# PnP-Expansion-V1.net
KiCad netlist of a schematic drawn in EAGLE
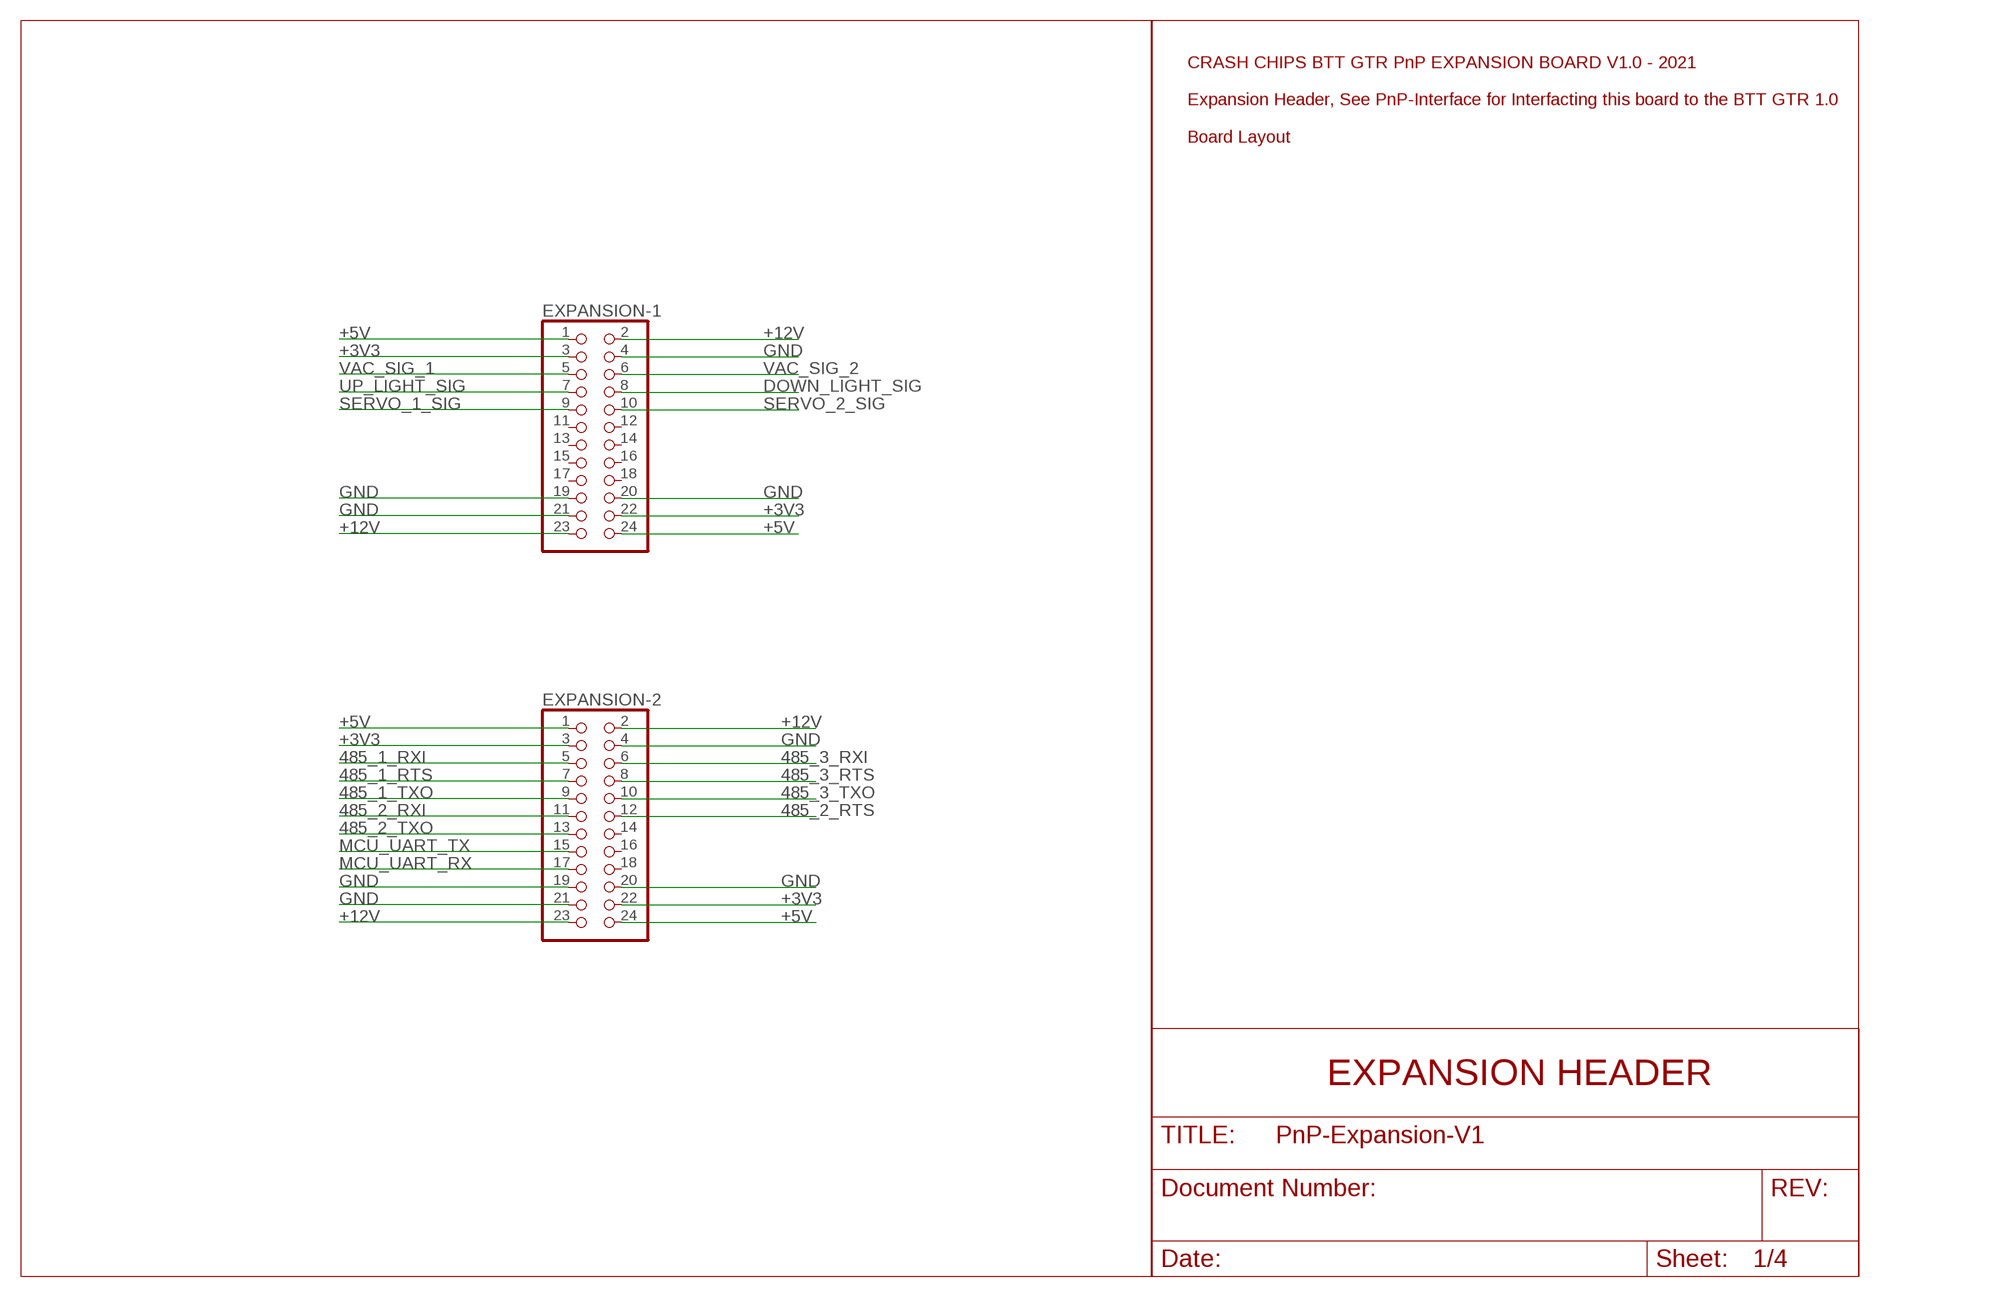
[diagram p0: schematic, sheet 1]
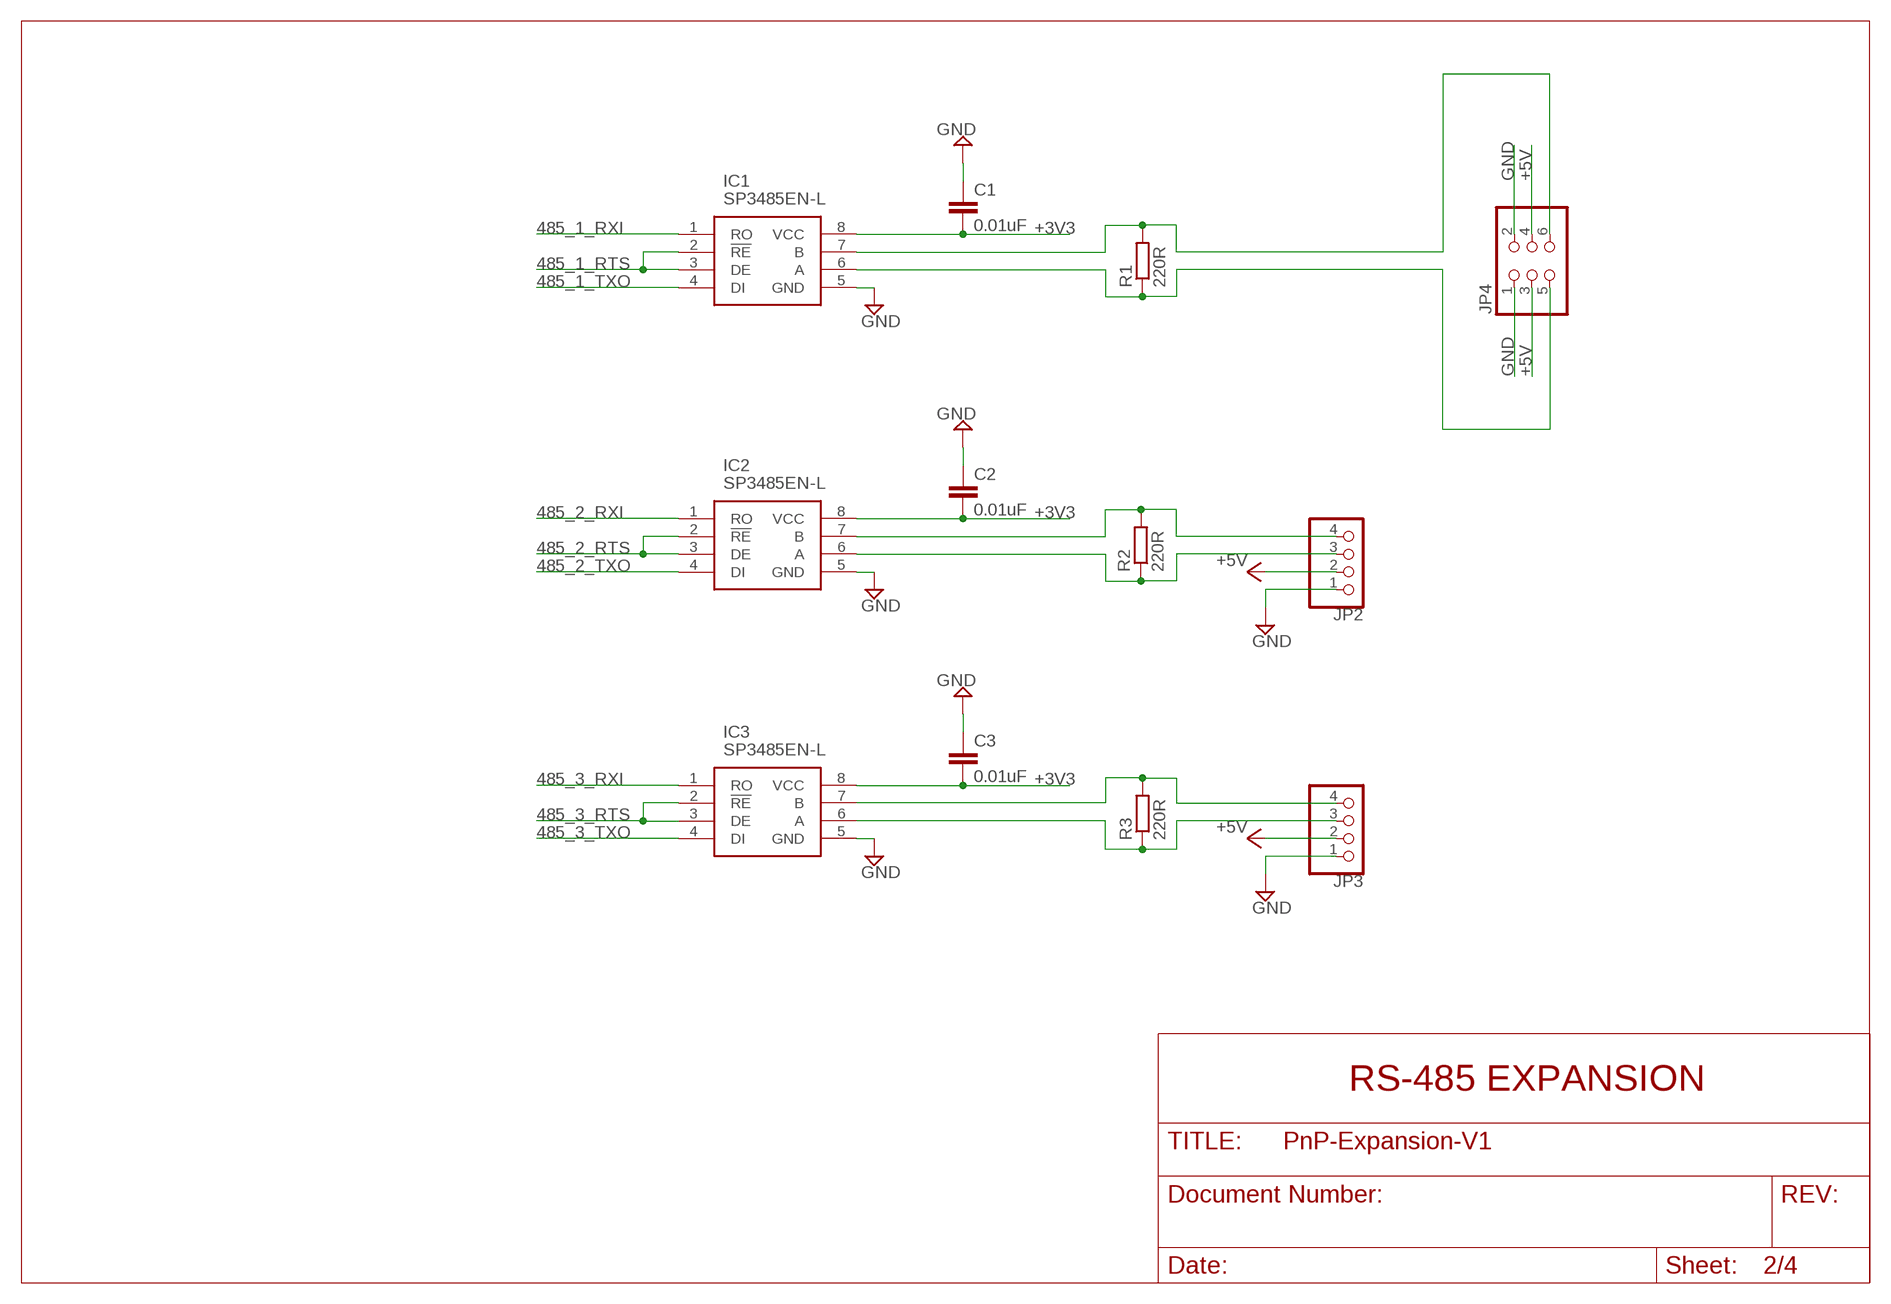
[diagram p1: schematic, sheet 2]
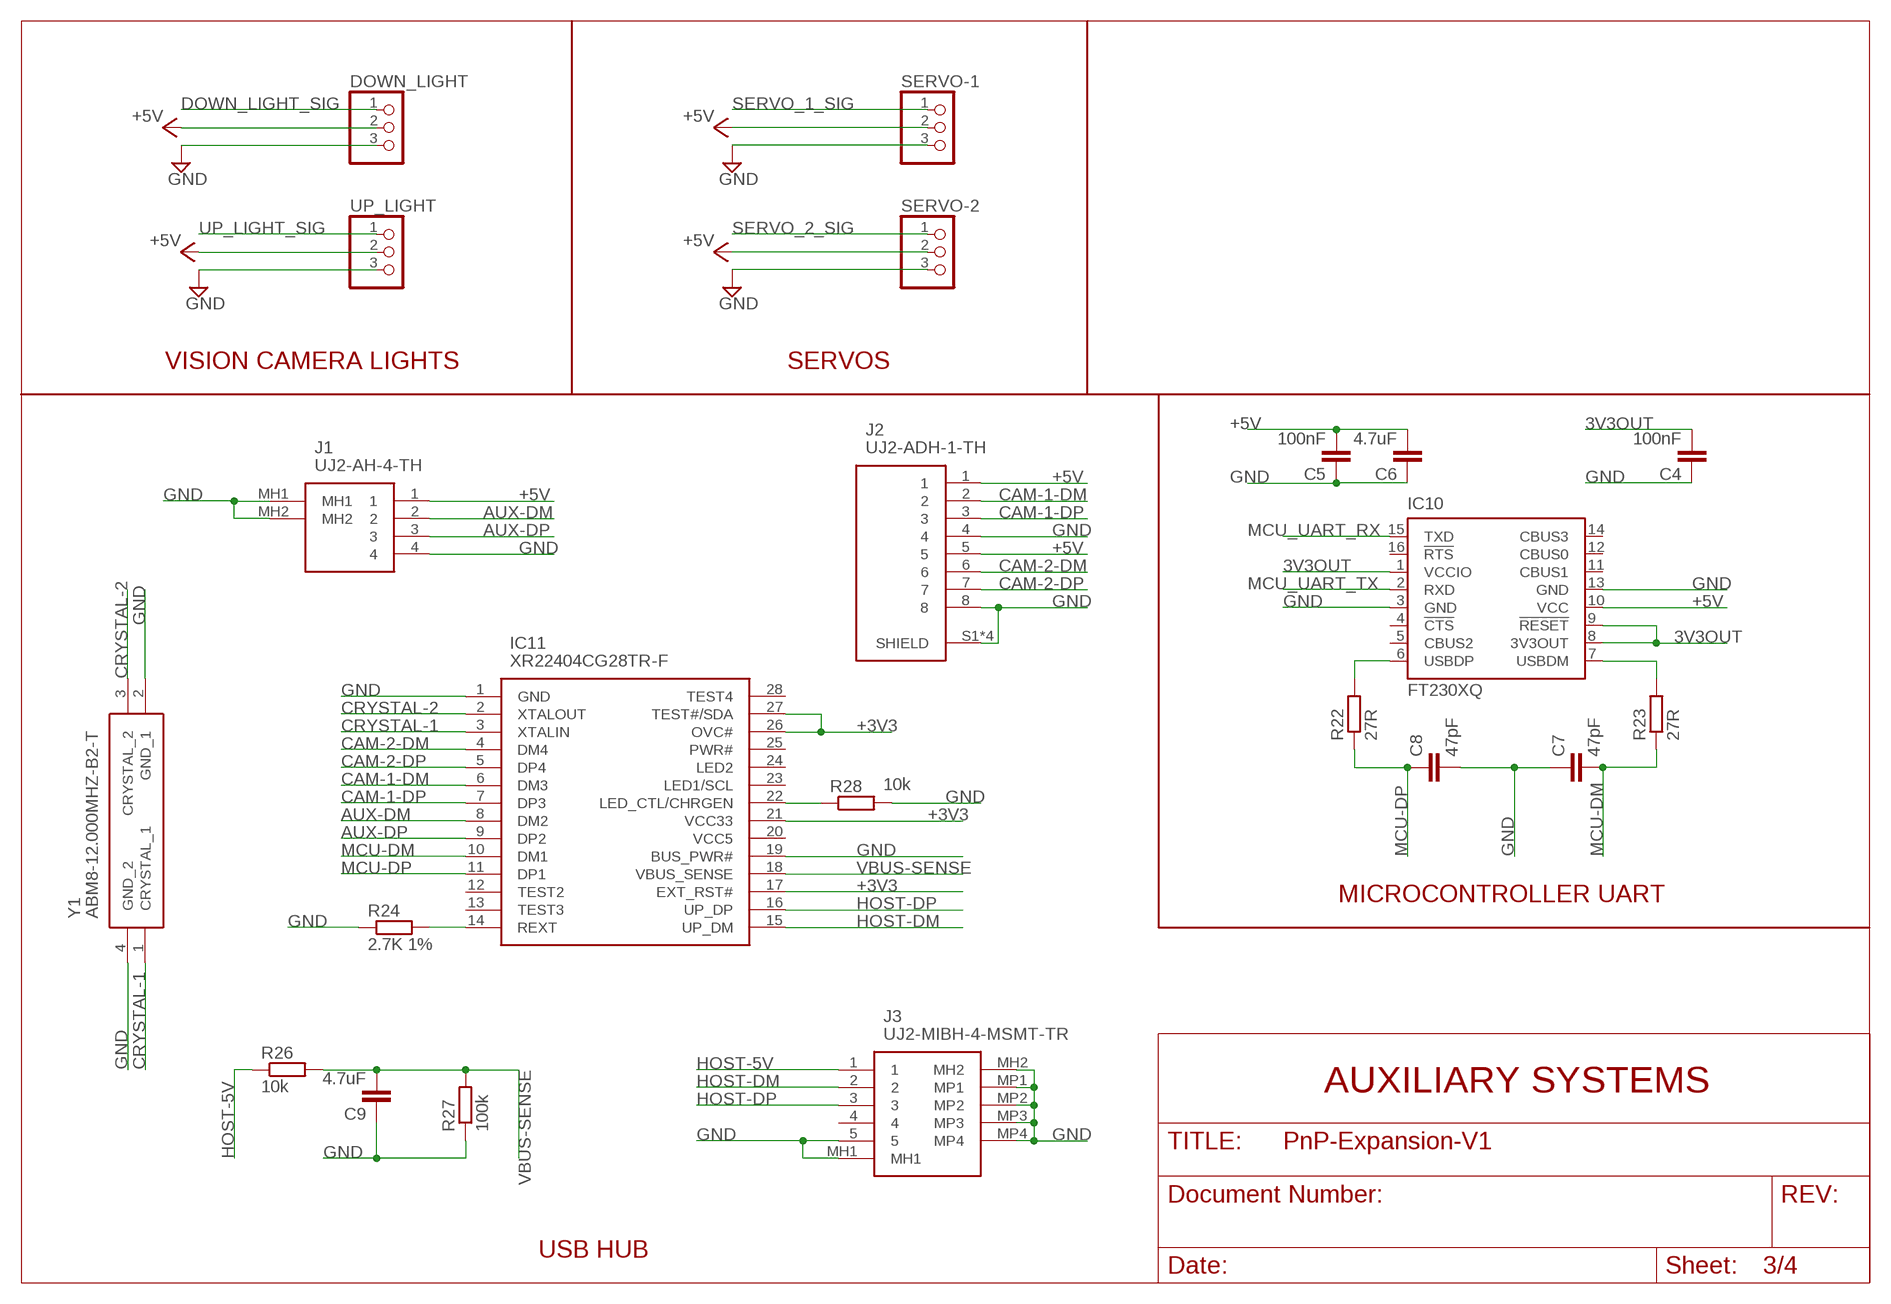
[diagram p2: schematic, sheet 3]
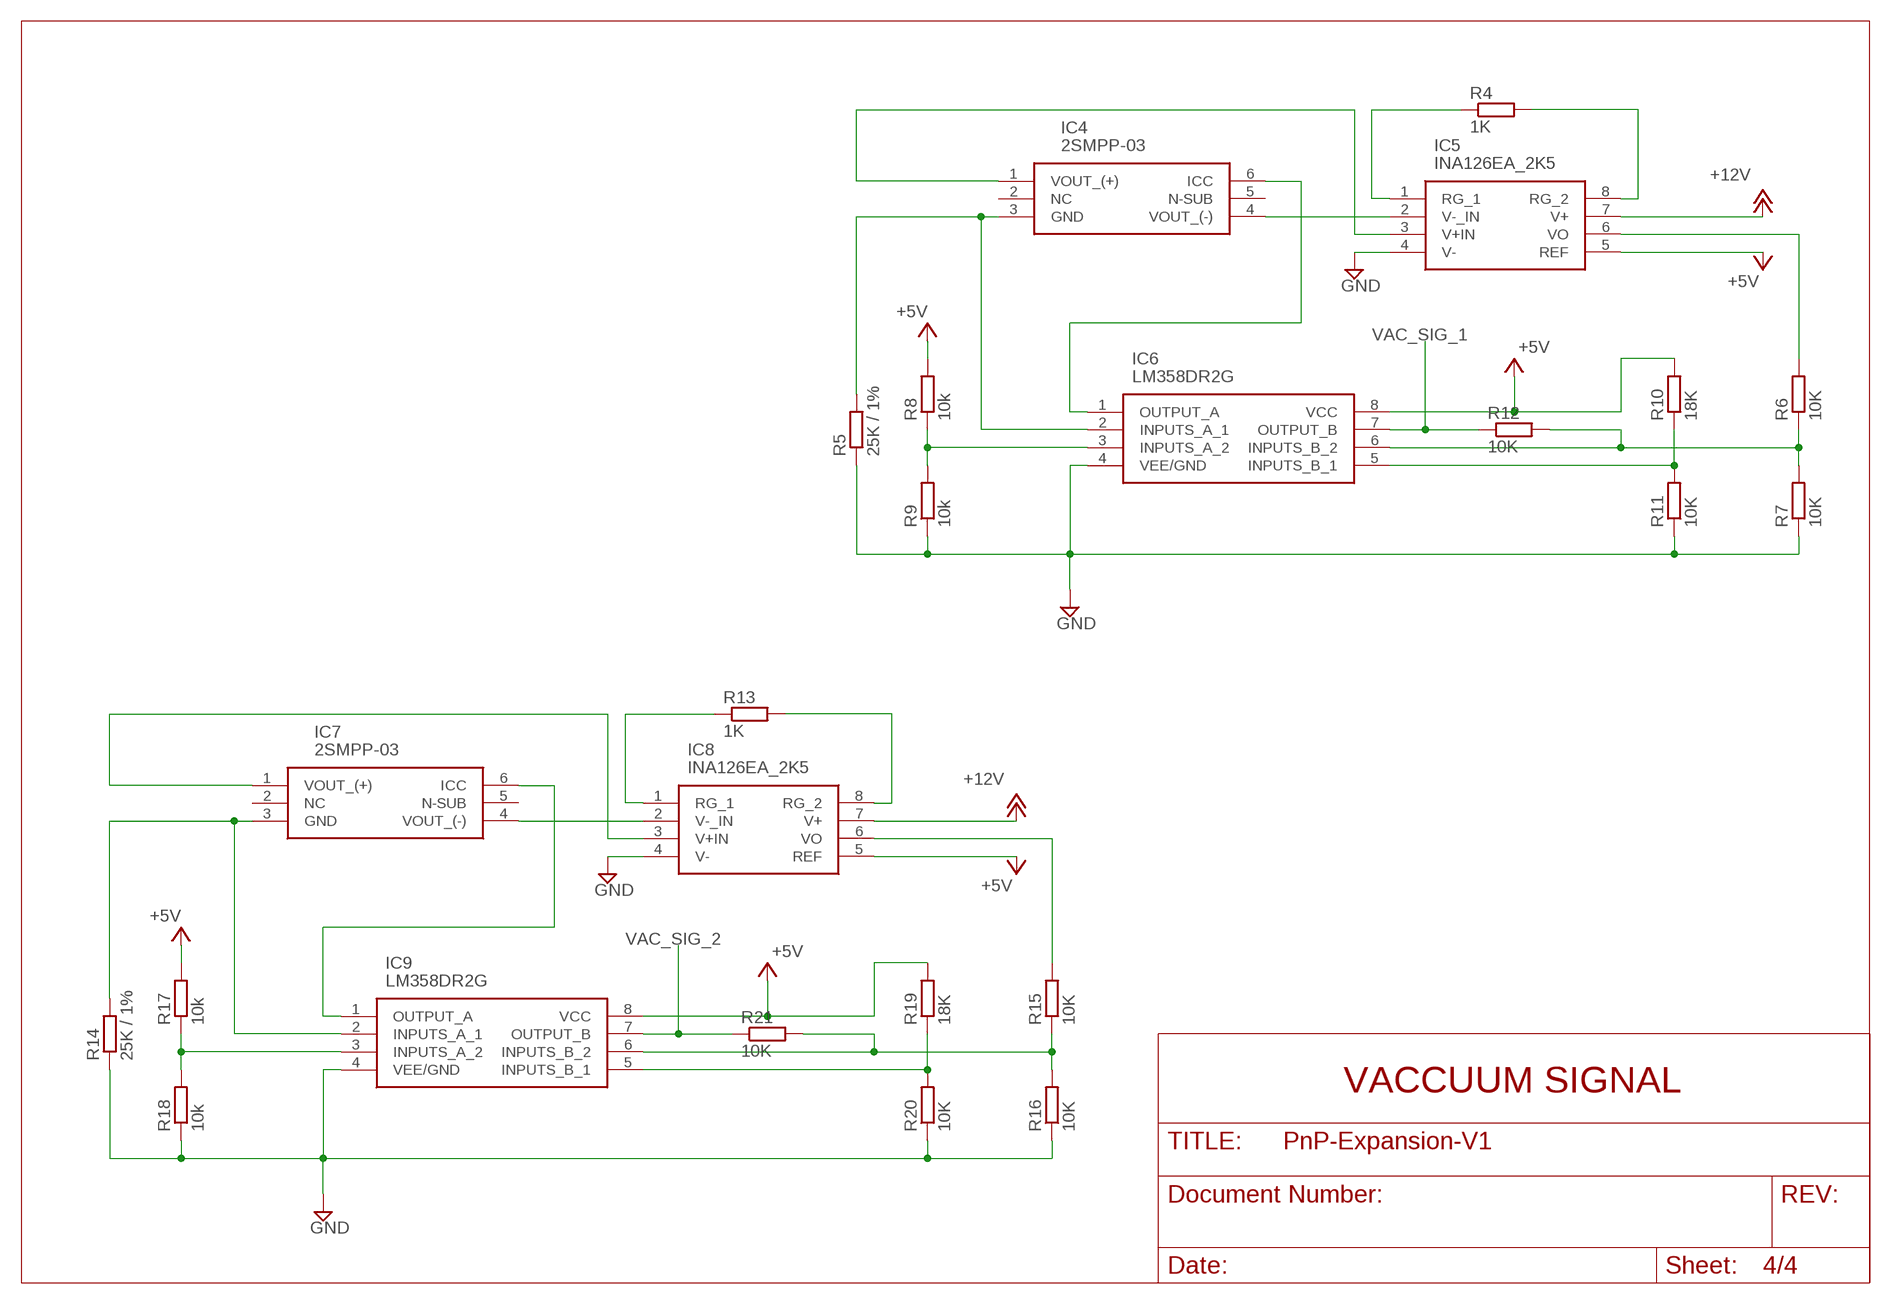
[diagram p3: schematic, sheet 4]

(export (version "E")
  (design (tool "Eeschema 10.0.6"))
  (components
    (comp (ref "IC4")
      (value "2SMPP-03")
      (footprint "eagle-import:2SMPP03")
      (fields (field (name "MOUSER_PART_NUMBER") "653-2SMPP-03"))
      (libsource (lib "eagle-import") (part "2SMPP-03"))
    )
    (comp (ref "IC5")
      (value "INA126EA_2K5")
      (footprint "eagle-import:SOP65P490X110-8N")
      (fields
        (field (name "ARROW_PART_NUMBER") "INA126EA/2K5")
        (field (name "MOUSER_PART_NUMBER") "595-INA126EA/2K5")
      )
      (libsource (lib "eagle-import") (part "INA126EA_2K5"))
    )
    (comp (ref "IC6")
      (value "LM358DR2G")
      (footprint "eagle-import:SOIC127P600X175-8N")
      (fields (field (name "MOUSER_PART_NUMBER") "863-LM358DR2G"))
      (libsource (lib "eagle-import") (part "LM358DR2G"))
    )
    (comp (ref "IC7")
      (value "2SMPP-03")
      (footprint "eagle-import:2SMPP03")
      (fields (field (name "MOUSER_PART_NUMBER") "653-2SMPP-03"))
      (libsource (lib "eagle-import") (part "2SMPP-03"))
    )
    (comp (ref "IC8")
      (value "INA126EA_2K5")
      (footprint "eagle-import:SOP65P490X110-8N")
      (fields
        (field (name "ARROW_PART_NUMBER") "INA126EA/2K5")
        (field (name "MOUSER_PART_NUMBER") "595-INA126EA/2K5")
      )
      (libsource (lib "eagle-import") (part "INA126EA_2K5"))
    )
    (comp (ref "IC9")
      (value "LM358DR2G")
      (footprint "eagle-import:SOIC127P600X175-8N")
      (fields (field (name "MOUSER_PART_NUMBER") "863-LM358DR2G"))
      (libsource (lib "eagle-import") (part "LM358DR2G"))
    )
    (comp (ref "R4")
      (value "1K")
      (footprint "eagle-import:M0805")
      (libsource (lib "eagle-import") (part "R-EU_M0805"))
    )
    (comp (ref "R5")
      (value "25K / 1%")
      (footprint "eagle-import:M0805")
      (libsource (lib "eagle-import") (part "R-EU_M0805"))
    )
    (comp (ref "R6")
      (value "10K")
      (footprint "eagle-import:M0805")
      (libsource (lib "eagle-import") (part "R-EU_M0805"))
    )
    (comp (ref "R7")
      (value "10K")
      (footprint "eagle-import:M0805")
      (libsource (lib "eagle-import") (part "R-EU_M0805"))
    )
    (comp (ref "R8")
      (value "10k")
      (footprint "eagle-import:M0805")
      (libsource (lib "eagle-import") (part "R-EU_M0805"))
    )
    (comp (ref "R9")
      (value "10k")
      (footprint "eagle-import:M0805")
      (libsource (lib "eagle-import") (part "R-EU_M0805"))
    )
    (comp (ref "R10")
      (value "18K")
      (footprint "eagle-import:M0805")
      (libsource (lib "eagle-import") (part "R-EU_M0805"))
    )
    (comp (ref "R11")
      (value "10K")
      (footprint "eagle-import:M0805")
      (libsource (lib "eagle-import") (part "R-EU_M0805"))
    )
    (comp (ref "R12")
      (value "10K")
      (footprint "eagle-import:M0805")
      (libsource (lib "eagle-import") (part "R-EU_M0805"))
    )
    (comp (ref "R13")
      (value "1K")
      (footprint "eagle-import:M0805")
      (libsource (lib "eagle-import") (part "R-EU_M0805"))
    )
    (comp (ref "R14")
      (value "25K / 1%")
      (footprint "eagle-import:M0805")
      (libsource (lib "eagle-import") (part "R-EU_M0805"))
    )
    (comp (ref "R15")
      (value "10K")
      (footprint "eagle-import:M0805")
      (libsource (lib "eagle-import") (part "R-EU_M0805"))
    )
    (comp (ref "R16")
      (value "10K")
      (footprint "eagle-import:M0805")
      (libsource (lib "eagle-import") (part "R-EU_M0805"))
    )
    (comp (ref "R17")
      (value "10k")
      (footprint "eagle-import:M0805")
      (libsource (lib "eagle-import") (part "R-EU_M0805"))
    )
    (comp (ref "R18")
      (value "10k")
      (footprint "eagle-import:M0805")
      (libsource (lib "eagle-import") (part "R-EU_M0805"))
    )
    (comp (ref "R19")
      (value "18K")
      (footprint "eagle-import:M0805")
      (libsource (lib "eagle-import") (part "R-EU_M0805"))
    )
    (comp (ref "R20")
      (value "10K")
      (footprint "eagle-import:M0805")
      (libsource (lib "eagle-import") (part "R-EU_M0805"))
    )
    (comp (ref "R21")
      (value "10K")
      (footprint "eagle-import:M0805")
      (libsource (lib "eagle-import") (part "R-EU_M0805"))
    )
    (comp (ref "EXPANSION-1")
      (value "PINHD-2X12")
      (footprint "eagle-import:2X12")
      (libsource (lib "eagle-import") (part "PINHD-2X12"))
    )
    (comp (ref "EXPANSION-2")
      (value "PINHD-2X12")
      (footprint "eagle-import:2X12")
      (libsource (lib "eagle-import") (part "PINHD-2X12"))
    )
    (comp (ref "C4")
      (value "100nF")
      (footprint "eagle-import:C0805")
      (libsource (lib "eagle-import") (part "C-EUC0805"))
    )
    (comp (ref "C5")
      (value "100nF")
      (footprint "eagle-import:C0805")
      (libsource (lib "eagle-import") (part "C-EUC0805"))
    )
    (comp (ref "C6")
      (value "4.7uF")
      (footprint "eagle-import:C0805")
      (libsource (lib "eagle-import") (part "C-EUC0805"))
    )
    (comp (ref "C7")
      (value "47pF")
      (footprint "eagle-import:C0805")
      (libsource (lib "eagle-import") (part "C-EUC0805"))
    )
    (comp (ref "C8")
      (value "47pF")
      (footprint "eagle-import:C0805")
      (libsource (lib "eagle-import") (part "C-EUC0805"))
    )
    (comp (ref "C9")
      (value "4.7uF")
      (footprint "eagle-import:C0805")
      (libsource (lib "eagle-import") (part "C-EUC0805"))
    )
    (comp (ref "DOWN_LIGHT")
      (value "PINHD-1X3")
      (footprint "eagle-import:1X03")
      (libsource (lib "eagle-import") (part "PINHD-1X3"))
    )
    (comp (ref "IC10")
      (value "FT230XQ")
      (footprint "eagle-import:QFN16")
      (libsource (lib "eagle-import") (part "FT230XQ"))
    )
    (comp (ref "IC11")
      (value "XR22404CG28TR-F")
      (footprint "eagle-import:SOP64P600X173-28N")
      (fields (field (name "MOUSER_PART_NUMBER") "701-XR22404CG28TR-F"))
      (libsource (lib "eagle-import") (part "XR22404CG28TR-F"))
    )
    (comp (ref "J1")
      (value "UJ2-AH-4-TH")
      (footprint "eagle-import:UJ2AH4TH")
      (fields (field (name "MOUSER_PART_NUMBER") "490-UJ2-AH-4-TH"))
      (libsource (lib "eagle-import") (part "UJ2-AH-4-TH"))
    )
    (comp (ref "J2")
      (value "UJ2-ADH-1-TH")
      (footprint "eagle-import:CUI_UJ2-ADH-1-TH")
      (fields (field (name "MANUFACTURER") "CUI Devices"))
      (libsource (lib "eagle-import") (part "UJ2-ADH-1-TH"))
    )
    (comp (ref "J3")
      (value "UJ2-MIBH-4-MSMT-TR")
      (footprint "eagle-import:UJ2MIBH4MSMTTR")
      (fields (field (name "MOUSER_PART_NUMBER") "490-UJ2-MIBH-4-MSMT"))
      (libsource (lib "eagle-import") (part "UJ2-MIBH-4-MSMT-TR"))
    )
    (comp (ref "R22")
      (value "27R")
      (footprint "eagle-import:M0805")
      (libsource (lib "eagle-import") (part "R-EU_M0805"))
    )
    (comp (ref "R23")
      (value "27R")
      (footprint "eagle-import:M0805")
      (libsource (lib "eagle-import") (part "R-EU_M0805"))
    )
    (comp (ref "R24")
      (value "2.7K 1%")
      (footprint "eagle-import:M0805")
      (libsource (lib "eagle-import") (part "R-EU_M0805"))
    )
    (comp (ref "R26")
      (value "10k")
      (footprint "eagle-import:M0805")
      (libsource (lib "eagle-import") (part "R-EU_M0805"))
    )
    (comp (ref "R27")
      (value "100k")
      (footprint "eagle-import:M0805")
      (libsource (lib "eagle-import") (part "R-EU_M0805"))
    )
    (comp (ref "R28")
      (value "10k")
      (footprint "eagle-import:M0805")
      (libsource (lib "eagle-import") (part "R-EU_M0805"))
    )
    (comp (ref "SERVO-1")
      (value "PINHD-1X3")
      (footprint "eagle-import:1X03")
      (libsource (lib "eagle-import") (part "PINHD-1X3"))
    )
    (comp (ref "SERVO-2")
      (value "PINHD-1X3")
      (footprint "eagle-import:1X03")
      (libsource (lib "eagle-import") (part "PINHD-1X3"))
    )
    (comp (ref "UP_LIGHT")
      (value "PINHD-1X3")
      (footprint "eagle-import:1X03")
      (libsource (lib "eagle-import") (part "PINHD-1X3"))
    )
    (comp (ref "Y1")
      (value "ABM8-12.000MHZ-B2-T")
      (footprint "eagle-import:ABM812000MHZB2T")
      (fields
        (field (name "MANUFACTURER_PART_NUMBER") "ABM8-12.000MHz-B2-T")
        (field (name "MOUSER_PART_NUMBER") "815-ABM8-12-B2-T")
      )
      (libsource (lib "eagle-import") (part "ABM8-12.000MHZ-B2-T"))
    )
    (comp (ref "C1")
      (value "0.01uF")
      (footprint "eagle-import:C0805")
      (libsource (lib "eagle-import") (part "C-EUC0805"))
    )
    (comp (ref "C2")
      (value "0.01uF")
      (footprint "eagle-import:C0805")
      (libsource (lib "eagle-import") (part "C-EUC0805"))
    )
    (comp (ref "C3")
      (value "0.01uF")
      (footprint "eagle-import:C0805")
      (libsource (lib "eagle-import") (part "C-EUC0805"))
    )
    (comp (ref "IC1")
      (value "SP3485EN-L")
      (footprint "eagle-import:SOIC127P600X175-8N")
      (fields (field (name "MOUSER_PART_NUMBER") "701-SP3485EN-L"))
      (libsource (lib "eagle-import") (part "SP3485EN-L"))
    )
    (comp (ref "IC2")
      (value "SP3485EN-L")
      (footprint "eagle-import:SOIC127P600X175-8N")
      (fields (field (name "MOUSER_PART_NUMBER") "701-SP3485EN-L"))
      (libsource (lib "eagle-import") (part "SP3485EN-L"))
    )
    (comp (ref "IC3")
      (value "SP3485EN-L")
      (footprint "eagle-import:SOIC127P600X175-8N")
      (fields (field (name "MOUSER_PART_NUMBER") "701-SP3485EN-L"))
      (libsource (lib "eagle-import") (part "SP3485EN-L"))
    )
    (comp (ref "JP2")
      (value "PINHD-1X4")
      (footprint "eagle-import:1X04")
      (libsource (lib "eagle-import") (part "PINHD-1X4"))
    )
    (comp (ref "JP3")
      (value "PINHD-1X4")
      (footprint "eagle-import:1X04")
      (libsource (lib "eagle-import") (part "PINHD-1X4"))
    )
    (comp (ref "JP4")
      (value "PINHD-2X3")
      (footprint "eagle-import:2X03")
      (libsource (lib "eagle-import") (part "PINHD-2X3"))
    )
    (comp (ref "R1")
      (value "220R")
      (footprint "eagle-import:M0805")
      (libsource (lib "eagle-import") (part "R-EU_M0805"))
    )
    (comp (ref "R2")
      (value "220R")
      (footprint "eagle-import:M0805")
      (libsource (lib "eagle-import") (part "R-EU_M0805"))
    )
    (comp (ref "R3")
      (value "220R")
      (footprint "eagle-import:M0805")
      (libsource (lib "eagle-import") (part "R-EU_M0805"))
    )
  )
  (nets
    (net (code "1") (name "+3V3") (class "Default")
      (node (ref "C1") (pin "2") (pinfunction "2_2") (pintype "passive"))
      (node (ref "C2") (pin "2") (pinfunction "2_2") (pintype "passive"))
      (node (ref "C3") (pin "2") (pinfunction "2_2") (pintype "passive"))
      (node (ref "EXPANSION-1") (pin "22") (pinfunction "22_22") (pintype "passive"))
      (node (ref "EXPANSION-1") (pin "3") (pinfunction "3_3") (pintype "passive"))
      (node (ref "EXPANSION-2") (pin "22") (pinfunction "22_22") (pintype "passive"))
      (node (ref "EXPANSION-2") (pin "3") (pinfunction "3_3") (pintype "passive"))
      (node (ref "IC1") (pin "8") (pinfunction "VCC_8") (pintype "power_in"))
      (node (ref "IC11") (pin "17") (pinfunction "EXT_RST#_17") (pintype "bidirectional"))
      (node (ref "IC11") (pin "21") (pinfunction "VCC33_21") (pintype "bidirectional"))
      (node (ref "IC11") (pin "26") (pinfunction "OVC#_26") (pintype "bidirectional"))
      (node (ref "IC11") (pin "27") (pinfunction "TEST#/SDA_27") (pintype "bidirectional"))
      (node (ref "IC2") (pin "8") (pinfunction "VCC_8") (pintype "power_in"))
      (node (ref "IC3") (pin "8") (pinfunction "VCC_8") (pintype "power_in"))
    )
    (net (code "2") (name "+5V") (class "Default")
      (node (ref "C5") (pin "2") (pinfunction "2_2") (pintype "passive"))
      (node (ref "C6") (pin "2") (pinfunction "2_2") (pintype "passive"))
      (node (ref "DOWN_LIGHT") (pin "2") (pinfunction "2_2") (pintype "passive"))
      (node (ref "EXPANSION-1") (pin "1") (pinfunction "1_1") (pintype "passive"))
      (node (ref "EXPANSION-1") (pin "24") (pinfunction "24_24") (pintype "passive"))
      (node (ref "EXPANSION-2") (pin "1") (pinfunction "1_1") (pintype "passive"))
      (node (ref "EXPANSION-2") (pin "24") (pinfunction "24_24") (pintype "passive"))
      (node (ref "IC10") (pin "10") (pinfunction "VCC_10") (pintype "power_in"))
      (node (ref "IC5") (pin "5") (pinfunction "REF_5") (pintype "bidirectional"))
      (node (ref "IC6") (pin "8") (pinfunction "VCC_8") (pintype "bidirectional"))
      (node (ref "IC8") (pin "5") (pinfunction "REF_5") (pintype "bidirectional"))
      (node (ref "IC9") (pin "8") (pinfunction "VCC_8") (pintype "bidirectional"))
      (node (ref "J1") (pin "1") (pinfunction "1_1") (pintype "bidirectional"))
      (node (ref "J2") (pin "1") (pinfunction "1_1") (pintype "passive"))
      (node (ref "J2") (pin "5") (pinfunction "5_5") (pintype "passive"))
      (node (ref "JP2") (pin "2") (pinfunction "2_2") (pintype "passive"))
      (node (ref "JP3") (pin "2") (pinfunction "2_2") (pintype "passive"))
      (node (ref "JP4") (pin "3") (pinfunction "3_3") (pintype "passive"))
      (node (ref "JP4") (pin "4") (pinfunction "4_4") (pintype "passive"))
      (node (ref "R10") (pin "2") (pinfunction "2_2") (pintype "passive"))
      (node (ref "R17") (pin "2") (pinfunction "2_2") (pintype "passive"))
      (node (ref "R19") (pin "2") (pinfunction "2_2") (pintype "passive"))
      (node (ref "R8") (pin "2") (pinfunction "2_2") (pintype "passive"))
      (node (ref "SERVO-1") (pin "2") (pinfunction "2_2") (pintype "passive"))
      (node (ref "SERVO-2") (pin "2") (pinfunction "2_2") (pintype "passive"))
      (node (ref "UP_LIGHT") (pin "2") (pinfunction "2_2") (pintype "passive"))
    )
    (net (code "3") (name "+12V") (class "Default")
      (node (ref "EXPANSION-1") (pin "2") (pinfunction "2_2") (pintype "passive"))
      (node (ref "EXPANSION-1") (pin "23") (pinfunction "23_23") (pintype "passive"))
      (node (ref "EXPANSION-2") (pin "2") (pinfunction "2_2") (pintype "passive"))
      (node (ref "EXPANSION-2") (pin "23") (pinfunction "23_23") (pintype "passive"))
      (node (ref "IC5") (pin "7") (pinfunction "V+_7") (pintype "bidirectional"))
      (node (ref "IC8") (pin "7") (pinfunction "V+_7") (pintype "bidirectional"))
    )
    (net (code "4") (name "3V3OUT") (class "Default")
      (node (ref "C4") (pin "1") (pinfunction "1_1") (pintype "passive"))
      (node (ref "IC10") (pin "1") (pinfunction "VCCIO_1") (pintype "power_in"))
      (node (ref "IC10") (pin "8") (pinfunction "3V3OUT_8") (pintype "output"))
      (node (ref "IC10") (pin "9") (pinfunction "~{RESET}_9") (pintype "input"))
    )
    (net (code "5") (name "485_1_RTS") (class "Default")
      (node (ref "EXPANSION-2") (pin "7") (pinfunction "7_7") (pintype "passive"))
      (node (ref "IC1") (pin "2") (pinfunction "~{RE}_2") (pintype "bidirectional"))
      (node (ref "IC1") (pin "3") (pinfunction "DE_3") (pintype "bidirectional"))
    )
    (net (code "6") (name "485_1_RXI") (class "Default")
      (node (ref "EXPANSION-2") (pin "5") (pinfunction "5_5") (pintype "passive"))
      (node (ref "IC1") (pin "1") (pinfunction "RO_1") (pintype "bidirectional"))
    )
    (net (code "7") (name "485_1_TXO") (class "Default")
      (node (ref "EXPANSION-2") (pin "9") (pinfunction "9_9") (pintype "passive"))
      (node (ref "IC1") (pin "4") (pinfunction "DI_4") (pintype "bidirectional"))
    )
    (net (code "8") (name "485_2_RTS") (class "Default")
      (node (ref "EXPANSION-2") (pin "12") (pinfunction "12_12") (pintype "passive"))
      (node (ref "IC2") (pin "2") (pinfunction "~{RE}_2") (pintype "bidirectional"))
      (node (ref "IC2") (pin "3") (pinfunction "DE_3") (pintype "bidirectional"))
    )
    (net (code "9") (name "485_2_RXI") (class "Default")
      (node (ref "EXPANSION-2") (pin "11") (pinfunction "11_11") (pintype "passive"))
      (node (ref "IC2") (pin "1") (pinfunction "RO_1") (pintype "bidirectional"))
    )
    (net (code "10") (name "485_2_TXO") (class "Default")
      (node (ref "EXPANSION-2") (pin "13") (pinfunction "13_13") (pintype "passive"))
      (node (ref "IC2") (pin "4") (pinfunction "DI_4") (pintype "bidirectional"))
    )
    (net (code "11") (name "485_3_RTS") (class "Default")
      (node (ref "EXPANSION-2") (pin "8") (pinfunction "8_8") (pintype "passive"))
      (node (ref "IC3") (pin "2") (pinfunction "~{RE}_2") (pintype "bidirectional"))
      (node (ref "IC3") (pin "3") (pinfunction "DE_3") (pintype "bidirectional"))
    )
    (net (code "12") (name "485_3_RXI") (class "Default")
      (node (ref "EXPANSION-2") (pin "6") (pinfunction "6_6") (pintype "passive"))
      (node (ref "IC3") (pin "1") (pinfunction "RO_1") (pintype "bidirectional"))
    )
    (net (code "13") (name "485_3_TXO") (class "Default")
      (node (ref "EXPANSION-2") (pin "10") (pinfunction "10_10") (pintype "passive"))
      (node (ref "IC3") (pin "4") (pinfunction "DI_4") (pintype "bidirectional"))
    )
    (net (code "14") (name "AUX-DM") (class "Default")
      (node (ref "IC11") (pin "8") (pinfunction "DM2_8") (pintype "bidirectional"))
      (node (ref "J1") (pin "2") (pinfunction "2_2") (pintype "bidirectional"))
    )
    (net (code "15") (name "AUX-DP") (class "Default")
      (node (ref "IC11") (pin "9") (pinfunction "DP2_9") (pintype "bidirectional"))
      (node (ref "J1") (pin "3") (pinfunction "3_3") (pintype "bidirectional"))
    )
    (net (code "16") (name "CAM-1-DM") (class "Default")
      (node (ref "IC11") (pin "6") (pinfunction "DM3_6") (pintype "bidirectional"))
      (node (ref "J2") (pin "2") (pinfunction "2_2") (pintype "passive"))
    )
    (net (code "17") (name "CAM-1-DP") (class "Default")
      (node (ref "IC11") (pin "7") (pinfunction "DP3_7") (pintype "bidirectional"))
      (node (ref "J2") (pin "3") (pinfunction "3_3") (pintype "passive"))
    )
    (net (code "18") (name "CAM-2-DM") (class "Default")
      (node (ref "IC11") (pin "4") (pinfunction "DM4_4") (pintype "bidirectional"))
      (node (ref "J2") (pin "6") (pinfunction "6_6") (pintype "passive"))
    )
    (net (code "19") (name "CAM-2-DP") (class "Default")
      (node (ref "IC11") (pin "5") (pinfunction "DP4_5") (pintype "bidirectional"))
      (node (ref "J2") (pin "7") (pinfunction "7_7") (pintype "passive"))
    )
    (net (code "20") (name "CRYSTAL-1") (class "Default")
      (node (ref "IC11") (pin "3") (pinfunction "XTALIN_3") (pintype "bidirectional"))
      (node (ref "Y1") (pin "1") (pinfunction "CRYSTAL_1_1") (pintype "bidirectional"))
    )
    (net (code "21") (name "CRYSTAL-2") (class "Default")
      (node (ref "IC11") (pin "2") (pinfunction "XTALOUT_2") (pintype "bidirectional"))
      (node (ref "Y1") (pin "3") (pinfunction "CRYSTAL_2_3") (pintype "bidirectional"))
    )
    (net (code "22") (name "DOWN_LIGHT_SIG") (class "Default")
      (node (ref "DOWN_LIGHT") (pin "1") (pinfunction "1_1") (pintype "passive"))
      (node (ref "EXPANSION-1") (pin "8") (pinfunction "8_8") (pintype "passive"))
    )
    (net (code "23") (name "GND") (class "Default")
      (node (ref "C1") (pin "1") (pinfunction "1_1") (pintype "passive"))
      (node (ref "C2") (pin "1") (pinfunction "1_1") (pintype "passive"))
      (node (ref "C3") (pin "1") (pinfunction "1_1") (pintype "passive"))
      (node (ref "C4") (pin "2") (pinfunction "2_2") (pintype "passive"))
      (node (ref "C5") (pin "1") (pinfunction "1_1") (pintype "passive"))
      (node (ref "C6") (pin "1") (pinfunction "1_1") (pintype "passive"))
      (node (ref "C7") (pin "1") (pinfunction "1_1") (pintype "passive"))
      (node (ref "C8") (pin "2") (pinfunction "2_2") (pintype "passive"))
      (node (ref "C9") (pin "1") (pinfunction "1_1") (pintype "passive"))
      (node (ref "DOWN_LIGHT") (pin "3") (pinfunction "3_3") (pintype "passive"))
      (node (ref "EXPANSION-1") (pin "19") (pinfunction "19_19") (pintype "passive"))
      (node (ref "EXPANSION-1") (pin "20") (pinfunction "20_20") (pintype "passive"))
      (node (ref "EXPANSION-1") (pin "21") (pinfunction "21_21") (pintype "passive"))
      (node (ref "EXPANSION-1") (pin "4") (pinfunction "4_4") (pintype "passive"))
      (node (ref "EXPANSION-2") (pin "19") (pinfunction "19_19") (pintype "passive"))
      (node (ref "EXPANSION-2") (pin "20") (pinfunction "20_20") (pintype "passive"))
      (node (ref "EXPANSION-2") (pin "21") (pinfunction "21_21") (pintype "passive"))
      (node (ref "EXPANSION-2") (pin "4") (pinfunction "4_4") (pintype "passive"))
      (node (ref "IC1") (pin "5") (pinfunction "GND_5") (pintype "power_in"))
      (node (ref "IC10") (pin "13") (pinfunction "GND_13") (pintype "power_in"))
      (node (ref "IC10") (pin "3") (pinfunction "GND_3") (pintype "power_in"))
      (node (ref "IC11") (pin "1") (pinfunction "GND_1") (pintype "power_in"))
      (node (ref "IC11") (pin "19") (pinfunction "BUS_PWR#_19") (pintype "bidirectional"))
      (node (ref "IC2") (pin "5") (pinfunction "GND_5") (pintype "power_in"))
      (node (ref "IC3") (pin "5") (pinfunction "GND_5") (pintype "power_in"))
      (node (ref "IC5") (pin "4") (pinfunction "V-_4") (pintype "bidirectional"))
      (node (ref "IC6") (pin "4") (pinfunction "VEE/GND_4") (pintype "bidirectional"))
      (node (ref "IC8") (pin "4") (pinfunction "V-_4") (pintype "bidirectional"))
      (node (ref "IC9") (pin "4") (pinfunction "VEE/GND_4") (pintype "bidirectional"))
      (node (ref "J1") (pin "4") (pinfunction "4_4") (pintype "bidirectional"))
      (node (ref "J1") (pin "MH1") (pinfunction "MH1_MH1") (pintype "bidirectional"))
      (node (ref "J1") (pin "MH2") (pinfunction "MH2_MH2") (pintype "bidirectional"))
      (node (ref "J2") (pin "4") (pinfunction "4_4") (pintype "passive"))
      (node (ref "J2") (pin "8") (pinfunction "8_8") (pintype "passive"))
      (node (ref "J2") (pin "S1") (pinfunction "SHIELD_S1") (pintype "passive"))
      (node (ref "J2") (pin "S2") (pinfunction "SHIELD_S2") (pintype "passive"))
      (node (ref "J2") (pin "S3") (pinfunction "SHIELD_S3") (pintype "passive"))
      (node (ref "J2") (pin "S4") (pinfunction "SHIELD_S4") (pintype "passive"))
      (node (ref "J3") (pin "5") (pinfunction "5_5") (pintype "bidirectional"))
      (node (ref "J3") (pin "MH1") (pinfunction "MH1_MH1") (pintype "bidirectional"))
      (node (ref "J3") (pin "MH2") (pinfunction "MH2_MH2") (pintype "bidirectional"))
      (node (ref "J3") (pin "MP1") (pinfunction "MP1_MP1") (pintype "bidirectional"))
      (node (ref "J3") (pin "MP2") (pinfunction "MP2_MP2") (pintype "bidirectional"))
      (node (ref "J3") (pin "MP3") (pinfunction "MP3_MP3") (pintype "bidirectional"))
      (node (ref "J3") (pin "MP4") (pinfunction "MP4_MP4") (pintype "bidirectional"))
      (node (ref "JP2") (pin "1") (pinfunction "1_1") (pintype "passive"))
      (node (ref "JP3") (pin "1") (pinfunction "1_1") (pintype "passive"))
      (node (ref "JP4") (pin "1") (pinfunction "1_1") (pintype "passive"))
      (node (ref "JP4") (pin "2") (pinfunction "2_2") (pintype "passive"))
      (node (ref "R11") (pin "1") (pinfunction "1_1") (pintype "passive"))
      (node (ref "R14") (pin "1") (pinfunction "1_1") (pintype "passive"))
      (node (ref "R16") (pin "1") (pinfunction "1_1") (pintype "passive"))
      (node (ref "R18") (pin "1") (pinfunction "1_1") (pintype "passive"))
      (node (ref "R20") (pin "1") (pinfunction "1_1") (pintype "passive"))
      (node (ref "R24") (pin "1") (pinfunction "1_1") (pintype "passive"))
      (node (ref "R27") (pin "1") (pinfunction "1_1") (pintype "passive"))
      (node (ref "R28") (pin "2") (pinfunction "2_2") (pintype "passive"))
      (node (ref "R5") (pin "1") (pinfunction "1_1") (pintype "passive"))
      (node (ref "R7") (pin "1") (pinfunction "1_1") (pintype "passive"))
      (node (ref "R9") (pin "1") (pinfunction "1_1") (pintype "passive"))
      (node (ref "SERVO-1") (pin "3") (pinfunction "3_3") (pintype "passive"))
      (node (ref "SERVO-2") (pin "3") (pinfunction "3_3") (pintype "passive"))
      (node (ref "UP_LIGHT") (pin "3") (pinfunction "3_3") (pintype "passive"))
      (node (ref "Y1") (pin "2") (pinfunction "GND_1_2") (pintype "bidirectional"))
      (node (ref "Y1") (pin "4") (pinfunction "GND_2_4") (pintype "bidirectional"))
    )
    (net (code "24") (name "HOST-5V") (class "Default")
      (node (ref "J3") (pin "1") (pinfunction "1_1") (pintype "bidirectional"))
      (node (ref "R26") (pin "1") (pinfunction "1_1") (pintype "passive"))
    )
    (net (code "25") (name "HOST-DM") (class "Default")
      (node (ref "IC11") (pin "15") (pinfunction "UP_DM_15") (pintype "bidirectional"))
      (node (ref "J3") (pin "2") (pinfunction "2_2") (pintype "bidirectional"))
    )
    (net (code "26") (name "HOST-DP") (class "Default")
      (node (ref "IC11") (pin "16") (pinfunction "UP_DP_16") (pintype "bidirectional"))
      (node (ref "J3") (pin "3") (pinfunction "3_3") (pintype "bidirectional"))
    )
    (net (code "27") (name "MCU-DM") (class "Default")
      (node (ref "C7") (pin "2") (pinfunction "2_2") (pintype "passive"))
      (node (ref "IC11") (pin "10") (pinfunction "DM1_10") (pintype "bidirectional"))
      (node (ref "R23") (pin "1") (pinfunction "1_1") (pintype "passive"))
    )
    (net (code "28") (name "MCU-DP") (class "Default")
      (node (ref "C8") (pin "1") (pinfunction "1_1") (pintype "passive"))
      (node (ref "IC11") (pin "11") (pinfunction "DP1_11") (pintype "bidirectional"))
      (node (ref "R22") (pin "1") (pinfunction "1_1") (pintype "passive"))
    )
    (net (code "29") (name "MCU_UART_RX") (class "Default")
      (node (ref "EXPANSION-2") (pin "17") (pinfunction "17_17") (pintype "passive"))
      (node (ref "IC10") (pin "15") (pinfunction "TXD_15") (pintype "output"))
    )
    (net (code "30") (name "MCU_UART_TX") (class "Default")
      (node (ref "EXPANSION-2") (pin "15") (pinfunction "15_15") (pintype "passive"))
      (node (ref "IC10") (pin "2") (pinfunction "RXD_2") (pintype "input"))
    )
    (net (code "31") (name "Net-(IC1-A)") (class "Default")
      (node (ref "IC1") (pin "6") (pinfunction "A_6") (pintype "bidirectional"))
      (node (ref "JP4") (pin "5") (pinfunction "5_5") (pintype "passive"))
      (node (ref "R1") (pin "1") (pinfunction "1_1") (pintype "passive"))
    )
    (net (code "32") (name "Net-(IC1-B)") (class "Default")
      (node (ref "IC1") (pin "7") (pinfunction "B_7") (pintype "bidirectional"))
      (node (ref "JP4") (pin "6") (pinfunction "6_6") (pintype "passive"))
      (node (ref "R1") (pin "2") (pinfunction "2_2") (pintype "passive"))
    )
    (net (code "33") (name "Net-(IC2-A)") (class "Default")
      (node (ref "IC2") (pin "6") (pinfunction "A_6") (pintype "bidirectional"))
      (node (ref "JP2") (pin "3") (pinfunction "3_3") (pintype "passive"))
      (node (ref "R2") (pin "1") (pinfunction "1_1") (pintype "passive"))
    )
    (net (code "34") (name "Net-(IC2-B)") (class "Default")
      (node (ref "IC2") (pin "7") (pinfunction "B_7") (pintype "bidirectional"))
      (node (ref "JP2") (pin "4") (pinfunction "4_4") (pintype "passive"))
      (node (ref "R2") (pin "2") (pinfunction "2_2") (pintype "passive"))
    )
    (net (code "35") (name "Net-(IC3-A)") (class "Default")
      (node (ref "IC3") (pin "6") (pinfunction "A_6") (pintype "bidirectional"))
      (node (ref "JP3") (pin "3") (pinfunction "3_3") (pintype "passive"))
      (node (ref "R3") (pin "1") (pinfunction "1_1") (pintype "passive"))
    )
    (net (code "36") (name "Net-(IC3-B)") (class "Default")
      (node (ref "IC3") (pin "7") (pinfunction "B_7") (pintype "bidirectional"))
      (node (ref "JP3") (pin "4") (pinfunction "4_4") (pintype "passive"))
      (node (ref "R3") (pin "2") (pinfunction "2_2") (pintype "passive"))
    )
    (net (code "37") (name "Net-(IC4-GND)") (class "Default")
      (node (ref "IC4") (pin "3") (pinfunction "GND_3") (pintype "bidirectional"))
      (node (ref "IC6") (pin "2") (pinfunction "INPUTS_A_1_2") (pintype "bidirectional"))
      (node (ref "R5") (pin "2") (pinfunction "2_2") (pintype "passive"))
    )
    (net (code "38") (name "Net-(IC4-ICC)") (class "Default")
      (node (ref "IC4") (pin "6") (pinfunction "ICC_6") (pintype "bidirectional"))
      (node (ref "IC6") (pin "1") (pinfunction "OUTPUT_A_1") (pintype "bidirectional"))
    )
    (net (code "39") (name "Net-(IC4-VOUT_(+))") (class "Default")
      (node (ref "IC4") (pin "1") (pinfunction "VOUT_(+)_1") (pintype "bidirectional"))
      (node (ref "IC5") (pin "3") (pinfunction "V+IN_3") (pintype "bidirectional"))
    )
    (net (code "40") (name "Net-(IC4-VOUT_(-))") (class "Default")
      (node (ref "IC4") (pin "4") (pinfunction "VOUT_(-)_4") (pintype "bidirectional"))
      (node (ref "IC5") (pin "2") (pinfunction "V-_IN_2") (pintype "bidirectional"))
    )
    (net (code "41") (name "Net-(IC5-RG_1)") (class "Default")
      (node (ref "IC5") (pin "1") (pinfunction "RG_1_1") (pintype "bidirectional"))
      (node (ref "R4") (pin "1") (pinfunction "1_1") (pintype "passive"))
    )
    (net (code "42") (name "Net-(IC5-RG_2)") (class "Default")
      (node (ref "IC5") (pin "8") (pinfunction "RG_2_8") (pintype "bidirectional"))
      (node (ref "R4") (pin "2") (pinfunction "2_2") (pintype "passive"))
    )
    (net (code "43") (name "Net-(IC5-VO)") (class "Default")
      (node (ref "IC5") (pin "6") (pinfunction "VO_6") (pintype "bidirectional"))
      (node (ref "R6") (pin "2") (pinfunction "2_2") (pintype "passive"))
    )
    (net (code "44") (name "Net-(IC6-INPUTS_A_2)") (class "Default")
      (node (ref "IC6") (pin "3") (pinfunction "INPUTS_A_2_3") (pintype "bidirectional"))
      (node (ref "R8") (pin "1") (pinfunction "1_1") (pintype "passive"))
      (node (ref "R9") (pin "2") (pinfunction "2_2") (pintype "passive"))
    )
    (net (code "45") (name "Net-(IC6-INPUTS_B_1)") (class "Default")
      (node (ref "IC6") (pin "5") (pinfunction "INPUTS_B_1_5") (pintype "bidirectional"))
      (node (ref "R10") (pin "1") (pinfunction "1_1") (pintype "passive"))
      (node (ref "R11") (pin "2") (pinfunction "2_2") (pintype "passive"))
    )
    (net (code "46") (name "Net-(IC6-INPUTS_B_2)") (class "Default")
      (node (ref "IC6") (pin "6") (pinfunction "INPUTS_B_2_6") (pintype "bidirectional"))
      (node (ref "R12") (pin "2") (pinfunction "2_2") (pintype "passive"))
      (node (ref "R6") (pin "1") (pinfunction "1_1") (pintype "passive"))
      (node (ref "R7") (pin "2") (pinfunction "2_2") (pintype "passive"))
    )
    (net (code "47") (name "Net-(IC7-GND)") (class "Default")
      (node (ref "IC7") (pin "3") (pinfunction "GND_3") (pintype "bidirectional"))
      (node (ref "IC9") (pin "2") (pinfunction "INPUTS_A_1_2") (pintype "bidirectional"))
      (node (ref "R14") (pin "2") (pinfunction "2_2") (pintype "passive"))
    )
    (net (code "48") (name "Net-(IC7-ICC)") (class "Default")
      (node (ref "IC7") (pin "6") (pinfunction "ICC_6") (pintype "bidirectional"))
      (node (ref "IC9") (pin "1") (pinfunction "OUTPUT_A_1") (pintype "bidirectional"))
    )
    (net (code "49") (name "Net-(IC7-VOUT_(+))") (class "Default")
      (node (ref "IC7") (pin "1") (pinfunction "VOUT_(+)_1") (pintype "bidirectional"))
      (node (ref "IC8") (pin "3") (pinfunction "V+IN_3") (pintype "bidirectional"))
    )
    (net (code "50") (name "Net-(IC7-VOUT_(-))") (class "Default")
      (node (ref "IC7") (pin "4") (pinfunction "VOUT_(-)_4") (pintype "bidirectional"))
      (node (ref "IC8") (pin "2") (pinfunction "V-_IN_2") (pintype "bidirectional"))
    )
    (net (code "51") (name "Net-(IC8-RG_1)") (class "Default")
      (node (ref "IC8") (pin "1") (pinfunction "RG_1_1") (pintype "bidirectional"))
      (node (ref "R13") (pin "1") (pinfunction "1_1") (pintype "passive"))
    )
    (net (code "52") (name "Net-(IC8-RG_2)") (class "Default")
      (node (ref "IC8") (pin "8") (pinfunction "RG_2_8") (pintype "bidirectional"))
      (node (ref "R13") (pin "2") (pinfunction "2_2") (pintype "passive"))
    )
    (net (code "53") (name "Net-(IC8-VO)") (class "Default")
      (node (ref "IC8") (pin "6") (pinfunction "VO_6") (pintype "bidirectional"))
      (node (ref "R15") (pin "2") (pinfunction "2_2") (pintype "passive"))
    )
    (net (code "54") (name "Net-(IC9-INPUTS_A_2)") (class "Default")
      (node (ref "IC9") (pin "3") (pinfunction "INPUTS_A_2_3") (pintype "bidirectional"))
      (node (ref "R17") (pin "1") (pinfunction "1_1") (pintype "passive"))
      (node (ref "R18") (pin "2") (pinfunction "2_2") (pintype "passive"))
    )
    (net (code "55") (name "Net-(IC9-INPUTS_B_1)") (class "Default")
      (node (ref "IC9") (pin "5") (pinfunction "INPUTS_B_1_5") (pintype "bidirectional"))
      (node (ref "R19") (pin "1") (pinfunction "1_1") (pintype "passive"))
      (node (ref "R20") (pin "2") (pinfunction "2_2") (pintype "passive"))
    )
    (net (code "56") (name "Net-(IC9-INPUTS_B_2)") (class "Default")
      (node (ref "IC9") (pin "6") (pinfunction "INPUTS_B_2_6") (pintype "bidirectional"))
      (node (ref "R15") (pin "1") (pinfunction "1_1") (pintype "passive"))
      (node (ref "R16") (pin "2") (pinfunction "2_2") (pintype "passive"))
      (node (ref "R21") (pin "2") (pinfunction "2_2") (pintype "passive"))
    )
    (net (code "57") (name "Net-(IC10-USBDM)") (class "Default")
      (node (ref "IC10") (pin "7") (pinfunction "USBDM_7") (pintype "input"))
      (node (ref "R23") (pin "2") (pinfunction "2_2") (pintype "passive"))
    )
    (net (code "58") (name "Net-(IC10-USBDP)") (class "Default")
      (node (ref "IC10") (pin "6") (pinfunction "USBDP_6") (pintype "input"))
      (node (ref "R22") (pin "2") (pinfunction "2_2") (pintype "passive"))
    )
    (net (code "59") (name "Net-(IC11-LED_CTL{slash}CHRGEN)") (class "Default")
      (node (ref "IC11") (pin "22") (pinfunction "LED_CTL/CHRGEN_22") (pintype "bidirectional"))
      (node (ref "R28") (pin "1") (pinfunction "1_1") (pintype "passive"))
    )
    (net (code "60") (name "Net-(IC11-REXT)") (class "Default")
      (node (ref "IC11") (pin "14") (pinfunction "REXT_14") (pintype "bidirectional"))
      (node (ref "R24") (pin "2") (pinfunction "2_2") (pintype "passive"))
    )
    (net (code "61") (name "SERVO_1_SIG") (class "Default")
      (node (ref "EXPANSION-1") (pin "9") (pinfunction "9_9") (pintype "passive"))
      (node (ref "SERVO-1") (pin "1") (pinfunction "1_1") (pintype "passive"))
    )
    (net (code "62") (name "SERVO_2_SIG") (class "Default")
      (node (ref "EXPANSION-1") (pin "10") (pinfunction "10_10") (pintype "passive"))
      (node (ref "SERVO-2") (pin "1") (pinfunction "1_1") (pintype "passive"))
    )
    (net (code "63") (name "UP_LIGHT_SIG") (class "Default")
      (node (ref "EXPANSION-1") (pin "7") (pinfunction "7_7") (pintype "passive"))
      (node (ref "UP_LIGHT") (pin "1") (pinfunction "1_1") (pintype "passive"))
    )
    (net (code "64") (name "VAC_SIG_1") (class "Default")
      (node (ref "EXPANSION-1") (pin "5") (pinfunction "5_5") (pintype "passive"))
      (node (ref "IC6") (pin "7") (pinfunction "OUTPUT_B_7") (pintype "bidirectional"))
      (node (ref "R12") (pin "1") (pinfunction "1_1") (pintype "passive"))
    )
    (net (code "65") (name "VAC_SIG_2") (class "Default")
      (node (ref "EXPANSION-1") (pin "6") (pinfunction "6_6") (pintype "passive"))
      (node (ref "IC9") (pin "7") (pinfunction "OUTPUT_B_7") (pintype "bidirectional"))
      (node (ref "R21") (pin "1") (pinfunction "1_1") (pintype "passive"))
    )
    (net (code "66") (name "VBUS-SENSE") (class "Default")
      (node (ref "C9") (pin "2") (pinfunction "2_2") (pintype "passive"))
      (node (ref "IC11") (pin "18") (pinfunction "VBUS_SENSE_18") (pintype "bidirectional"))
      (node (ref "R26") (pin "2") (pinfunction "2_2") (pintype "passive"))
      (node (ref "R27") (pin "2") (pinfunction "2_2") (pintype "passive"))
    )
    (net (code "67") (name "unconnected-(EXPANSION-1-Pad11)") (class "Default")
      (node (ref "EXPANSION-1") (pin "11") (pinfunction "11_11") (pintype "passive"))
    )
    (net (code "68") (name "unconnected-(EXPANSION-1-Pad12)") (class "Default")
      (node (ref "EXPANSION-1") (pin "12") (pinfunction "12_12") (pintype "passive"))
    )
    (net (code "69") (name "unconnected-(EXPANSION-1-Pad13)") (class "Default")
      (node (ref "EXPANSION-1") (pin "13") (pinfunction "13_13") (pintype "passive"))
    )
    (net (code "70") (name "unconnected-(EXPANSION-1-Pad14)") (class "Default")
      (node (ref "EXPANSION-1") (pin "14") (pinfunction "14_14") (pintype "passive"))
    )
    (net (code "71") (name "unconnected-(EXPANSION-1-Pad15)") (class "Default")
      (node (ref "EXPANSION-1") (pin "15") (pinfunction "15_15") (pintype "passive"))
    )
    (net (code "72") (name "unconnected-(EXPANSION-1-Pad16)") (class "Default")
      (node (ref "EXPANSION-1") (pin "16") (pinfunction "16_16") (pintype "passive"))
    )
    (net (code "73") (name "unconnected-(EXPANSION-1-Pad17)") (class "Default")
      (node (ref "EXPANSION-1") (pin "17") (pinfunction "17_17") (pintype "passive"))
    )
    (net (code "74") (name "unconnected-(EXPANSION-1-Pad18)") (class "Default")
      (node (ref "EXPANSION-1") (pin "18") (pinfunction "18_18") (pintype "passive"))
    )
    (net (code "75") (name "unconnected-(EXPANSION-2-Pad14)") (class "Default")
      (node (ref "EXPANSION-2") (pin "14") (pinfunction "14_14") (pintype "passive"))
    )
    (net (code "76") (name "unconnected-(EXPANSION-2-Pad16)") (class "Default")
      (node (ref "EXPANSION-2") (pin "16") (pinfunction "16_16") (pintype "passive"))
    )
    (net (code "77") (name "unconnected-(EXPANSION-2-Pad18)") (class "Default")
      (node (ref "EXPANSION-2") (pin "18") (pinfunction "18_18") (pintype "passive"))
    )
    (net (code "78") (name "unconnected-(IC4-N-SUB-Pad5)") (class "Default")
      (node (ref "IC4") (pin "5") (pinfunction "N-SUB_5") (pintype "bidirectional"))
    )
    (net (code "79") (name "unconnected-(IC4-NC-Pad2)") (class "Default")
      (node (ref "IC4") (pin "2") (pinfunction "NC_2") (pintype "no_connect"))
    )
    (net (code "80") (name "unconnected-(IC7-N-SUB-Pad5)") (class "Default")
      (node (ref "IC7") (pin "5") (pinfunction "N-SUB_5") (pintype "bidirectional"))
    )
    (net (code "81") (name "unconnected-(IC7-NC-Pad2)") (class "Default")
      (node (ref "IC7") (pin "2") (pinfunction "NC_2") (pintype "no_connect"))
    )
    (net (code "82") (name "unconnected-(IC10-CBUS0-Pad12)") (class "Default")
      (node (ref "IC10") (pin "12") (pinfunction "CBUS0_12") (pintype "bidirectional"))
    )
    (net (code "83") (name "unconnected-(IC10-CBUS1-Pad11)") (class "Default")
      (node (ref "IC10") (pin "11") (pinfunction "CBUS1_11") (pintype "bidirectional"))
    )
    (net (code "84") (name "unconnected-(IC10-CBUS2-Pad5)") (class "Default")
      (node (ref "IC10") (pin "5") (pinfunction "CBUS2_5") (pintype "bidirectional"))
    )
    (net (code "85") (name "unconnected-(IC10-CBUS3-Pad14)") (class "Default")
      (node (ref "IC10") (pin "14") (pinfunction "CBUS3_14") (pintype "bidirectional"))
    )
    (net (code "86") (name "unconnected-(IC10-~{CTS}-Pad4)") (class "Default")
      (node (ref "IC10") (pin "4") (pinfunction "~{CTS}_4") (pintype "input"))
    )
    (net (code "87") (name "unconnected-(IC10-~{RTS}-Pad16)") (class "Default")
      (node (ref "IC10") (pin "16") (pinfunction "~{RTS}_16") (pintype "output"))
    )
    (net (code "88") (name "unconnected-(IC11-LED1{slash}SCL-Pad23)") (class "Default")
      (node (ref "IC11") (pin "23") (pinfunction "LED1/SCL_23") (pintype "bidirectional"))
    )
    (net (code "89") (name "unconnected-(IC11-LED2-Pad24)") (class "Default")
      (node (ref "IC11") (pin "24") (pinfunction "LED2_24") (pintype "bidirectional"))
    )
    (net (code "90") (name "unconnected-(IC11-PWR#-Pad25)") (class "Default")
      (node (ref "IC11") (pin "25") (pinfunction "PWR#_25") (pintype "bidirectional"))
    )
    (net (code "91") (name "unconnected-(IC11-TEST2-Pad12)") (class "Default")
      (node (ref "IC11") (pin "12") (pinfunction "TEST2_12") (pintype "bidirectional"))
    )
    (net (code "92") (name "unconnected-(IC11-TEST3-Pad13)") (class "Default")
      (node (ref "IC11") (pin "13") (pinfunction "TEST3_13") (pintype "bidirectional"))
    )
    (net (code "93") (name "unconnected-(IC11-TEST4-Pad28)") (class "Default")
      (node (ref "IC11") (pin "28") (pinfunction "TEST4_28") (pintype "bidirectional"))
    )
    (net (code "94") (name "unconnected-(IC11-VCC5-Pad20)") (class "Default")
      (node (ref "IC11") (pin "20") (pinfunction "VCC5_20") (pintype "bidirectional"))
    )
    (net (code "95") (name "unconnected-(J3-Pad4)") (class "Default")
      (node (ref "J3") (pin "4") (pinfunction "4_4") (pintype "bidirectional"))
    )
  )
)
